# door_sensor.net
KiCad netlist of a schematic drawn in EAGLE
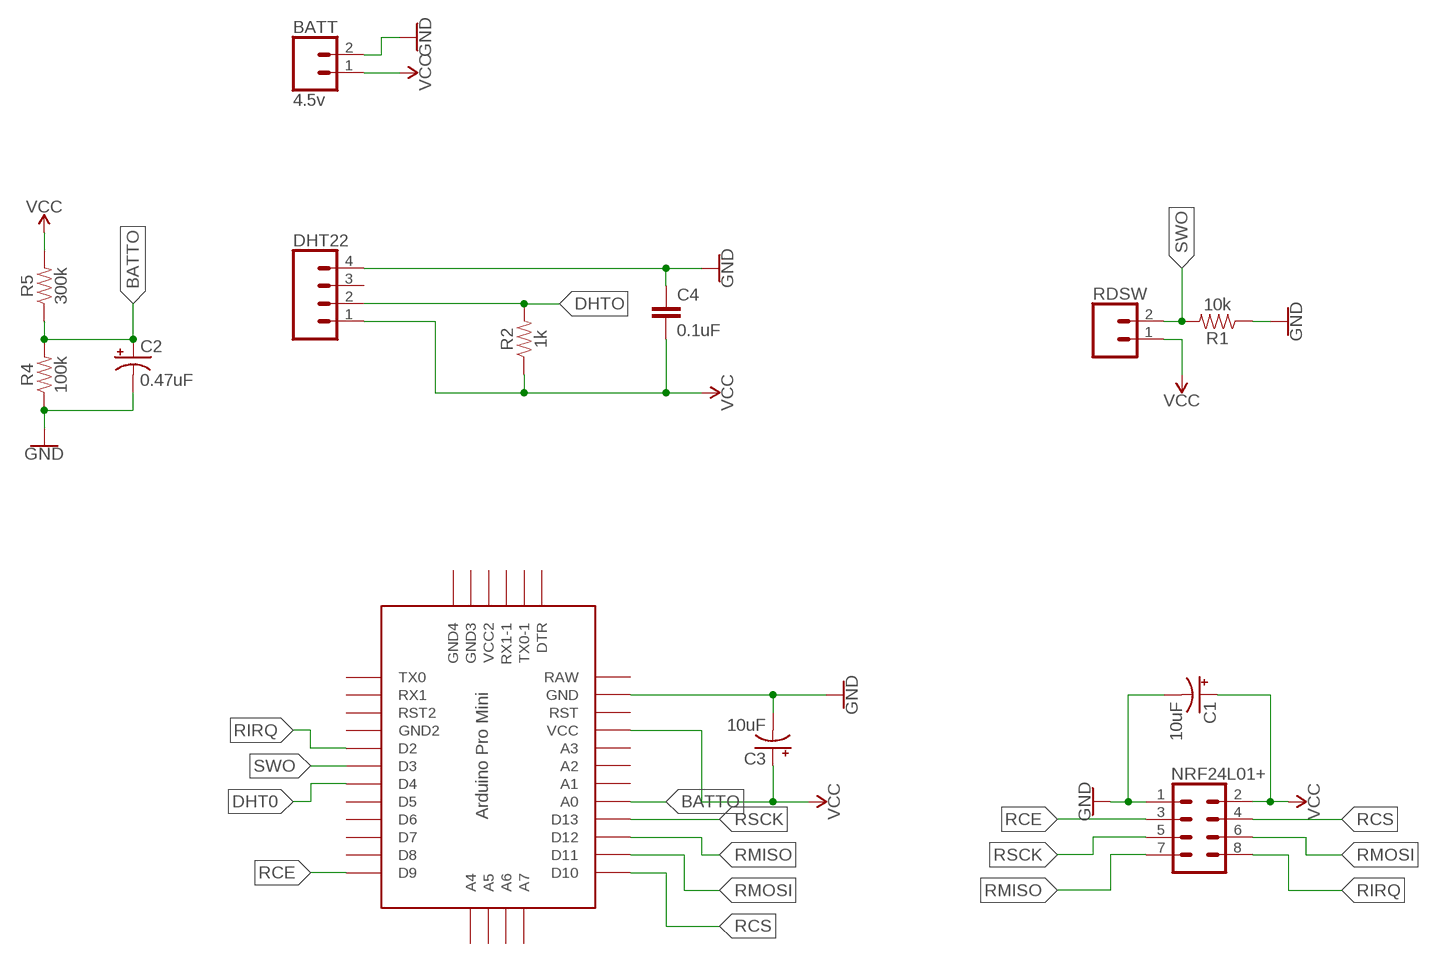
[diagram p0: schematic, sheet 1]

(export (version "E")
  (design (tool "Eeschema 10.0.6"))
  (components
    (comp (ref "BATT")
      (value "4.5v")
      (footprint "eagle-import:1X02")
      (libsource (lib "eagle-import") (part "CONN_02"))
    )
    (comp (ref "C1")
      (value "10uF")
      (footprint "eagle-import:CPOL-RADIAL-2.5MM-5MM")
      (libsource (lib "eagle-import") (part "10UF-POLAR-RADIAL-2.5MM-25V-20%"))
    )
    (comp (ref "C2")
      (value "0.47uF")
      (footprint "eagle-import:CPOL-RADIAL-2.5MM-5MM")
      (libsource (lib "eagle-import") (part "10UF-POLAR-RADIAL-2.5MM-25V-20%"))
    )
    (comp (ref "C3")
      (value "10uF")
      (footprint "eagle-import:CPOL-RADIAL-2.5MM-5MM")
      (libsource (lib "eagle-import") (part "10UF-POLAR-RADIAL-2.5MM-25V-20%"))
    )
    (comp (ref "C4")
      (value "0.1uF")
      (footprint "eagle-import:CAP-PTH-SMALL-KIT")
      (libsource (lib "eagle-import") (part "0.1UF-KIT-EZ-50V-20%"))
    )
    (comp (ref "DHT22")
      (value "CONN_04")
      (footprint "eagle-import:1X04")
      (libsource (lib "eagle-import") (part "CONN_04"))
    )
    (comp (ref "IC1")
      (value "PRO-MINI")
      (footprint "eagle-import:PRO-MINI")
      (libsource (lib "eagle-import") (part "PRO-MINI"))
    )
    (comp (ref "NRF24L01+")
      (value "CONN_04X2")
      (footprint "eagle-import:2X4")
      (libsource (lib "eagle-import") (part "CONN_04X2"))
    )
    (comp (ref "R1")
      (value "10k")
      (footprint "eagle-import:AXIAL-0.3")
      (libsource (lib "eagle-import") (part "10KOHM-HORIZ-1/4W-1%"))
    )
    (comp (ref "R2")
      (value "1k")
      (footprint "eagle-import:AXIAL-0.3")
      (libsource (lib "eagle-import") (part "1KOHM-HORIZ-1/4W-5%"))
    )
    (comp (ref "R4")
      (value "100k")
      (footprint "eagle-import:AXIAL-0.3")
      (libsource (lib "eagle-import") (part "100KOHM-HORIZ-1/4W-1%"))
    )
    (comp (ref "R5")
      (value "300k")
      (footprint "eagle-import:AXIAL-0.3")
      (libsource (lib "eagle-import") (part "RESISTORAXIAL-0.3"))
    )
    (comp (ref "RDSW")
      (value "CONN_02")
      (footprint "eagle-import:1X02")
      (libsource (lib "eagle-import") (part "CONN_02"))
    )
  )
  (nets
    (net (code "1") (name "/RAW") (class "Default")
      (node (ref "IC1") (pin "RAW") (pinfunction "RAW_RAW") (pintype "power_in"))
    )
    (net (code "2") (name "BATTO") (class "Default")
      (node (ref "C2") (pin "1") (pinfunction "+_1") (pintype "passive"))
      (node (ref "IC1") (pin "A0") (pinfunction "A0_A0") (pintype "bidirectional"))
      (node (ref "R4") (pin "P$2") (pinfunction "2_P$2") (pintype "passive"))
      (node (ref "R5") (pin "P$1") (pinfunction "1_P$1") (pintype "passive"))
    )
    (net (code "3") (name "DHT0") (class "Default")
      (node (ref "IC1") (pin "D4") (pinfunction "D4_D4") (pintype "bidirectional"))
    )
    (net (code "4") (name "DHTO") (class "Default")
      (node (ref "DHT22") (pin "2") (pinfunction "2_2") (pintype "passive"))
      (node (ref "R2") (pin "P$2") (pinfunction "2_P$2") (pintype "passive"))
    )
    (net (code "5") (name "GND") (class "Default")
      (node (ref "BATT") (pin "2") (pinfunction "2_2") (pintype "passive"))
      (node (ref "C1") (pin "2") (pinfunction "-_2") (pintype "passive"))
      (node (ref "C2") (pin "2") (pinfunction "-_2") (pintype "passive"))
      (node (ref "C3") (pin "2") (pinfunction "-_2") (pintype "passive"))
      (node (ref "C4") (pin "1") (pinfunction "1_1") (pintype "passive"))
      (node (ref "DHT22") (pin "4") (pinfunction "4_4") (pintype "passive"))
      (node (ref "IC1") (pin "GND") (pinfunction "GND_GND") (pintype "input"))
      (node (ref "NRF24L01+") (pin "1") (pinfunction "1_1") (pintype "passive"))
      (node (ref "R1") (pin "P$1") (pinfunction "1_P$1") (pintype "passive"))
      (node (ref "R4") (pin "P$1") (pinfunction "1_P$1") (pintype "passive"))
    )
    (net (code "6") (name "RCE") (class "Default")
      (node (ref "IC1") (pin "D9") (pinfunction "D9_D9") (pintype "bidirectional"))
      (node (ref "NRF24L01+") (pin "3") (pinfunction "3_3") (pintype "passive"))
    )
    (net (code "7") (name "RCS") (class "Default")
      (node (ref "IC1") (pin "D10") (pinfunction "D10_D10") (pintype "bidirectional"))
      (node (ref "NRF24L01+") (pin "4") (pinfunction "4_4") (pintype "passive"))
    )
    (net (code "8") (name "RIRQ") (class "Default")
      (node (ref "IC1") (pin "D2") (pinfunction "D2_D2") (pintype "bidirectional"))
      (node (ref "NRF24L01+") (pin "8") (pinfunction "8_8") (pintype "passive"))
    )
    (net (code "9") (name "RMISO") (class "Default")
      (node (ref "IC1") (pin "D12") (pinfunction "D12_D12") (pintype "bidirectional"))
      (node (ref "NRF24L01+") (pin "7") (pinfunction "7_7") (pintype "passive"))
    )
    (net (code "10") (name "RMOSI") (class "Default")
      (node (ref "IC1") (pin "D11") (pinfunction "D11_D11") (pintype "bidirectional"))
      (node (ref "NRF24L01+") (pin "6") (pinfunction "6_6") (pintype "passive"))
    )
    (net (code "11") (name "RSCK") (class "Default")
      (node (ref "IC1") (pin "D13") (pinfunction "D13_D13") (pintype "bidirectional"))
      (node (ref "NRF24L01+") (pin "5") (pinfunction "5_5") (pintype "passive"))
    )
    (net (code "12") (name "SWO") (class "Default")
      (node (ref "IC1") (pin "D3") (pinfunction "D3_D3") (pintype "bidirectional"))
      (node (ref "R1") (pin "P$2") (pinfunction "2_P$2") (pintype "passive"))
      (node (ref "RDSW") (pin "2") (pinfunction "2_2") (pintype "passive"))
    )
    (net (code "13") (name "VCC") (class "Default")
      (node (ref "BATT") (pin "1") (pinfunction "1_1") (pintype "passive"))
      (node (ref "C1") (pin "1") (pinfunction "+_1") (pintype "passive"))
      (node (ref "C3") (pin "1") (pinfunction "+_1") (pintype "passive"))
      (node (ref "C4") (pin "2") (pinfunction "2_2") (pintype "passive"))
      (node (ref "DHT22") (pin "1") (pinfunction "1_1") (pintype "passive"))
      (node (ref "IC1") (pin "VCC") (pinfunction "VCC_VCC") (pintype "bidirectional"))
      (node (ref "NRF24L01+") (pin "2") (pinfunction "2_2") (pintype "passive"))
      (node (ref "R2") (pin "P$1") (pinfunction "1_P$1") (pintype "passive"))
      (node (ref "R5") (pin "P$2") (pinfunction "2_P$2") (pintype "passive"))
      (node (ref "RDSW") (pin "1") (pinfunction "1_1") (pintype "passive"))
    )
    (net (code "14") (name "unconnected-(DHT22-Pad3)") (class "Default")
      (node (ref "DHT22") (pin "3") (pinfunction "3_3") (pintype "passive"))
    )
    (net (code "15") (name "unconnected-(IC1-GND2-PadGND1)") (class "Default")
      (node (ref "IC1") (pin "GND1") (pinfunction "GND2_GND1") (pintype "bidirectional"))
    )
    (net (code "16") (name "unconnected-(IC1-GND4-PadGND2)") (class "Default")
      (node (ref "IC1") (pin "GND2") (pinfunction "GND4_GND2") (pintype "bidirectional"))
    )
    (net (code "17") (name "unconnected-(IC1-PadA1)") (class "Default")
      (node (ref "IC1") (pin "A1") (pinfunction "A1_A1") (pintype "bidirectional"))
    )
    (net (code "18") (name "unconnected-(IC1-PadA2)") (class "Default")
      (node (ref "IC1") (pin "A2") (pinfunction "A2_A2") (pintype "bidirectional"))
    )
    (net (code "19") (name "unconnected-(IC1-PadA3)") (class "Default")
      (node (ref "IC1") (pin "A3") (pinfunction "A3_A3") (pintype "bidirectional"))
    )
    (net (code "20") (name "unconnected-(IC1-PadA4)") (class "Default")
      (node (ref "IC1") (pin "A4") (pinfunction "A4_A4") (pintype "bidirectional"))
    )
    (net (code "21") (name "unconnected-(IC1-PadA5)") (class "Default")
      (node (ref "IC1") (pin "A5") (pinfunction "A5_A5") (pintype "bidirectional"))
    )
    (net (code "22") (name "unconnected-(IC1-PadA6)") (class "Default")
      (node (ref "IC1") (pin "A6") (pinfunction "A6_A6") (pintype "bidirectional"))
    )
    (net (code "23") (name "unconnected-(IC1-PadA7)") (class "Default")
      (node (ref "IC1") (pin "A7") (pinfunction "A7_A7") (pintype "bidirectional"))
    )
    (net (code "24") (name "unconnected-(IC1-PadD5)") (class "Default")
      (node (ref "IC1") (pin "D5") (pinfunction "D5_D5") (pintype "bidirectional"))
    )
    (net (code "25") (name "unconnected-(IC1-PadD6)") (class "Default")
      (node (ref "IC1") (pin "D6") (pinfunction "D6_D6") (pintype "bidirectional"))
    )
    (net (code "26") (name "unconnected-(IC1-PadD7)") (class "Default")
      (node (ref "IC1") (pin "D7") (pinfunction "D7_D7") (pintype "bidirectional"))
    )
    (net (code "27") (name "unconnected-(IC1-PadD8)") (class "Default")
      (node (ref "IC1") (pin "D8") (pinfunction "D8_D8") (pintype "bidirectional"))
    )
    (net (code "28") (name "unconnected-(IC1-PadDTR)") (class "Default")
      (node (ref "IC1") (pin "DTR") (pinfunction "DTR_DTR") (pintype "bidirectional"))
    )
    (net (code "29") (name "unconnected-(IC1-PadGND3)") (class "Default")
      (node (ref "IC1") (pin "GND3") (pinfunction "GND3_GND3") (pintype "bidirectional"))
    )
    (net (code "30") (name "unconnected-(IC1-PadRST)") (class "Default")
      (node (ref "IC1") (pin "RST") (pinfunction "RST_RST") (pintype "bidirectional"))
    )
    (net (code "31") (name "unconnected-(IC1-PadRX1)") (class "Default")
      (node (ref "IC1") (pin "RX1") (pinfunction "RX1_RX1") (pintype "bidirectional"))
    )
    (net (code "32") (name "unconnected-(IC1-PadRX1-1)") (class "Default")
      (node (ref "IC1") (pin "RX1-1") (pinfunction "RX1-1_RX1-1") (pintype "bidirectional"))
    )
    (net (code "33") (name "unconnected-(IC1-PadTX0)") (class "Default")
      (node (ref "IC1") (pin "TX0") (pinfunction "TX0_TX0") (pintype "bidirectional"))
    )
    (net (code "34") (name "unconnected-(IC1-PadTX0-1)") (class "Default")
      (node (ref "IC1") (pin "TX0-1") (pinfunction "TX0-1_TX0-1") (pintype "bidirectional"))
    )
    (net (code "35") (name "unconnected-(IC1-RST2-PadRST1)") (class "Default")
      (node (ref "IC1") (pin "RST1") (pinfunction "RST2_RST1") (pintype "bidirectional"))
    )
    (net (code "36") (name "unconnected-(IC1-VCC2-PadVCC1)") (class "Default")
      (node (ref "IC1") (pin "VCC1") (pinfunction "VCC2_VCC1") (pintype "bidirectional"))
    )
  )
)
